# breakout.net
KiCad netlist of a schematic drawn in EAGLE
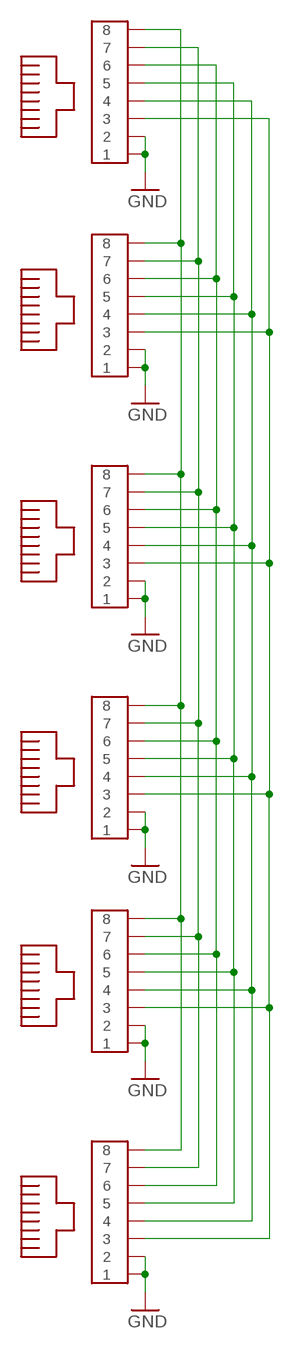
[diagram p0: schematic, sheet 1]

(export (version "E")
  (design (tool "Eeschema 10.0.6"))
  (components
    (comp (ref "U$1")
      (value "MOLEX-RJ45-SMT")
      (footprint "eagle-import:MOLEX-RJ45-SMT")
      (libsource (lib "eagle-import") (part "MOLEX-RJ45-SMT"))
    )
    (comp (ref "U$2")
      (value "MOLEX-RJ45-SMT")
      (footprint "eagle-import:MOLEX-RJ45-SMT")
      (libsource (lib "eagle-import") (part "MOLEX-RJ45-SMT"))
    )
    (comp (ref "U$3")
      (value "MOLEX-RJ45-SMT")
      (footprint "eagle-import:MOLEX-RJ45-SMT")
      (libsource (lib "eagle-import") (part "MOLEX-RJ45-SMT"))
    )
    (comp (ref "U$4")
      (value "MOLEX-RJ45-SMT")
      (footprint "eagle-import:MOLEX-RJ45-SMT")
      (libsource (lib "eagle-import") (part "MOLEX-RJ45-SMT"))
    )
    (comp (ref "U$5")
      (value "MOLEX-RJ45-SMT")
      (footprint "eagle-import:MOLEX-RJ45-SMT")
      (libsource (lib "eagle-import") (part "MOLEX-RJ45-SMT"))
    )
    (comp (ref "U$6")
      (value "MOLEX-RJ45-SMT")
      (footprint "eagle-import:MOLEX-RJ45-SMT")
      (libsource (lib "eagle-import") (part "MOLEX-RJ45-SMT"))
    )
  )
  (nets
    (net (code "1") (name "GND") (class "Default")
      (node (ref "U$1") (pin "1") (pinfunction "1_1") (pintype "bidirectional"))
      (node (ref "U$1") (pin "2") (pinfunction "2_2") (pintype "bidirectional"))
      (node (ref "U$2") (pin "1") (pinfunction "1_1") (pintype "bidirectional"))
      (node (ref "U$2") (pin "2") (pinfunction "2_2") (pintype "bidirectional"))
      (node (ref "U$3") (pin "1") (pinfunction "1_1") (pintype "bidirectional"))
      (node (ref "U$3") (pin "2") (pinfunction "2_2") (pintype "bidirectional"))
      (node (ref "U$4") (pin "1") (pinfunction "1_1") (pintype "bidirectional"))
      (node (ref "U$4") (pin "2") (pinfunction "2_2") (pintype "bidirectional"))
      (node (ref "U$5") (pin "1") (pinfunction "1_1") (pintype "bidirectional"))
      (node (ref "U$5") (pin "2") (pinfunction "2_2") (pintype "bidirectional"))
      (node (ref "U$6") (pin "1") (pinfunction "1_1") (pintype "bidirectional"))
      (node (ref "U$6") (pin "2") (pinfunction "2_2") (pintype "bidirectional"))
    )
    (net (code "2") (name "Net-(U$1-Pad3)") (class "Default")
      (node (ref "U$1") (pin "3") (pinfunction "3_3") (pintype "bidirectional"))
      (node (ref "U$2") (pin "3") (pinfunction "3_3") (pintype "bidirectional"))
      (node (ref "U$3") (pin "3") (pinfunction "3_3") (pintype "bidirectional"))
      (node (ref "U$4") (pin "3") (pinfunction "3_3") (pintype "bidirectional"))
      (node (ref "U$5") (pin "3") (pinfunction "3_3") (pintype "bidirectional"))
      (node (ref "U$6") (pin "3") (pinfunction "3_3") (pintype "bidirectional"))
    )
    (net (code "3") (name "Net-(U$1-Pad4)") (class "Default")
      (node (ref "U$1") (pin "4") (pinfunction "4_4") (pintype "bidirectional"))
      (node (ref "U$2") (pin "4") (pinfunction "4_4") (pintype "bidirectional"))
      (node (ref "U$3") (pin "4") (pinfunction "4_4") (pintype "bidirectional"))
      (node (ref "U$4") (pin "4") (pinfunction "4_4") (pintype "bidirectional"))
      (node (ref "U$5") (pin "4") (pinfunction "4_4") (pintype "bidirectional"))
      (node (ref "U$6") (pin "4") (pinfunction "4_4") (pintype "bidirectional"))
    )
    (net (code "4") (name "Net-(U$1-Pad5)") (class "Default")
      (node (ref "U$1") (pin "5") (pinfunction "5_5") (pintype "bidirectional"))
      (node (ref "U$2") (pin "5") (pinfunction "5_5") (pintype "bidirectional"))
      (node (ref "U$3") (pin "5") (pinfunction "5_5") (pintype "bidirectional"))
      (node (ref "U$4") (pin "5") (pinfunction "5_5") (pintype "bidirectional"))
      (node (ref "U$5") (pin "5") (pinfunction "5_5") (pintype "bidirectional"))
      (node (ref "U$6") (pin "5") (pinfunction "5_5") (pintype "bidirectional"))
    )
    (net (code "5") (name "Net-(U$1-Pad6)") (class "Default")
      (node (ref "U$1") (pin "6") (pinfunction "6_6") (pintype "bidirectional"))
      (node (ref "U$2") (pin "6") (pinfunction "6_6") (pintype "bidirectional"))
      (node (ref "U$3") (pin "6") (pinfunction "6_6") (pintype "bidirectional"))
      (node (ref "U$4") (pin "6") (pinfunction "6_6") (pintype "bidirectional"))
      (node (ref "U$5") (pin "6") (pinfunction "6_6") (pintype "bidirectional"))
      (node (ref "U$6") (pin "6") (pinfunction "6_6") (pintype "bidirectional"))
    )
    (net (code "6") (name "Net-(U$1-Pad7)") (class "Default")
      (node (ref "U$1") (pin "7") (pinfunction "7_7") (pintype "bidirectional"))
      (node (ref "U$2") (pin "7") (pinfunction "7_7") (pintype "bidirectional"))
      (node (ref "U$3") (pin "7") (pinfunction "7_7") (pintype "bidirectional"))
      (node (ref "U$4") (pin "7") (pinfunction "7_7") (pintype "bidirectional"))
      (node (ref "U$5") (pin "7") (pinfunction "7_7") (pintype "bidirectional"))
      (node (ref "U$6") (pin "7") (pinfunction "7_7") (pintype "bidirectional"))
    )
    (net (code "7") (name "Net-(U$1-Pad8)") (class "Default")
      (node (ref "U$1") (pin "8") (pinfunction "8_8") (pintype "bidirectional"))
      (node (ref "U$2") (pin "8") (pinfunction "8_8") (pintype "bidirectional"))
      (node (ref "U$3") (pin "8") (pinfunction "8_8") (pintype "bidirectional"))
      (node (ref "U$4") (pin "8") (pinfunction "8_8") (pintype "bidirectional"))
      (node (ref "U$5") (pin "8") (pinfunction "8_8") (pintype "bidirectional"))
      (node (ref "U$6") (pin "8") (pinfunction "8_8") (pintype "bidirectional"))
    )
  )
)
